# S4_-_MICROCONTROLLER.net
KiCad netlist of a schematic drawn in Altium Designer
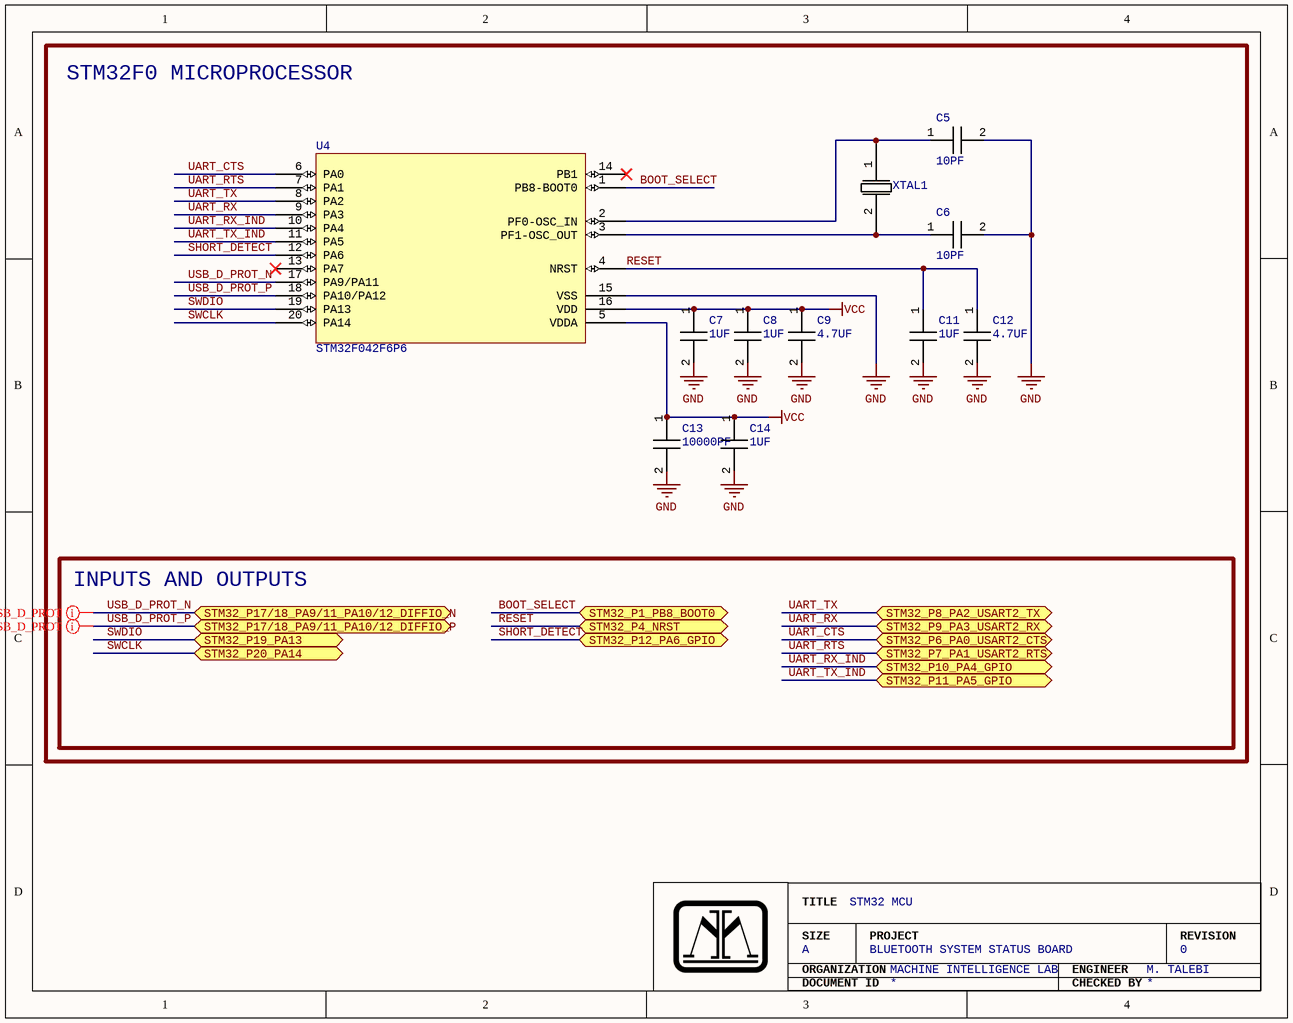
[diagram p0: S4 - MICROCONTROLLER.SchDoc]

(export (version "E")
  (design (tool "Eeschema 10.0.6"))
  (components
    (comp (ref "C5")
      (value "10PF")
      (footprint "C0603C0G1E100D030BA")
      (description "CAP CER 10PF 25V C0G 0201")
      (fields (field (name "TOLERANCE") "±0.5pF"))
      (libsource (lib "Master") (part "C0603C0G1E100D030BA"))
    )
    (comp (ref "C6")
      (value "10PF")
      (footprint "C0603C0G1E100D030BA")
      (description "CAP CER 10PF 25V C0G 0201")
      (fields (field (name "TOLERANCE") "±0.5pF"))
      (libsource (lib "Master") (part "C0603C0G1E100D030BA"))
    )
    (comp (ref "C7")
      (value "1UF")
      (footprint "CL10A105KQ8NNNC")
      (description "CAP CER 1UF 6.3V X5R 0603")
      (fields (field (name "TOLERANCE") "±10%"))
      (libsource (lib "Master") (part "CL10A105KQ8NNNC"))
    )
    (comp (ref "C8")
      (value "1UF")
      (footprint "CL10A105KQ8NNNC")
      (description "CAP CER 1UF 6.3V X5R 0603")
      (fields (field (name "TOLERANCE") "±10%"))
      (libsource (lib "Master") (part "CL10A105KQ8NNNC"))
    )
    (comp (ref "C9")
      (value "4.7UF")
      (footprint "TMK212AB7475KG-T")
      (description "CAP CER 4.7UF 25V X7R 0805")
      (fields (field (name "TOLERANCE") "±10%"))
      (libsource (lib "Master") (part "TMK212AB7475KG-T"))
    )
    (comp (ref "C11")
      (value "1UF")
      (footprint "CL10A105KQ8NNNC")
      (description "CAP CER 1UF 6.3V X5R 0603")
      (fields (field (name "TOLERANCE") "±10%"))
      (libsource (lib "Master") (part "CL10A105KQ8NNNC"))
    )
    (comp (ref "C12")
      (value "4.7UF")
      (footprint "TMK212AB7475KG-T")
      (description "CAP CER 4.7UF 25V X7R 0805")
      (fields (field (name "TOLERANCE") "±10%"))
      (libsource (lib "Master") (part "TMK212AB7475KG-T"))
    )
    (comp (ref "C13")
      (value "10000PF")
      (footprint "C1005X7R1C103K050BA")
      (description "CAP CER 10000PF 16V X7R 0402")
      (fields (field (name "TOLERANCE") "±10%"))
      (libsource (lib "Master") (part "C1005X7R1C103K050BA"))
    )
    (comp (ref "C14")
      (value "1UF")
      (footprint "CL10A105KQ8NNNC")
      (description "CAP CER 1UF 6.3V X5R 0603")
      (fields (field (name "TOLERANCE") "±10%"))
      (libsource (lib "Master") (part "CL10A105KQ8NNNC"))
    )
    (comp (ref "U4")
      (value "STM32F042F6P6")
      (footprint "STM32F042F6P6")
      (description "IC MCU 32BIT 32KB FLASH 20TSSOP")
      (libsource (lib "Master") (part "STM32F042F6P6"))
    )
    (comp (ref "XTAL1")
      (value "ECS-80-20-5PX-TR")
      (footprint "ECS-80-20-5PX-TR")
      (description "CRYSTAL 8.0000MHZ 20PF SMD")
      (libsource (lib "Master") (part "ECS-80-20-5PX-TR"))
    )
  )
  (nets
    (net (code "1") (name "/BOOT_SELECT") (class "Default")
      (node (ref "U4") (pin "1") (pinfunction "PB8-BOOT0_1") (pintype "bidirectional"))
    )
    (net (code "2") (name "/RESET") (class "Default")
      (node (ref "C11") (pin "1") (pinfunction "1_1") (pintype "passive"))
      (node (ref "C12") (pin "1") (pinfunction "1_1") (pintype "passive"))
      (node (ref "U4") (pin "4") (pinfunction "NRST_4") (pintype "bidirectional"))
    )
    (net (code "3") (name "/SHORT_DETECT") (class "Default")
      (node (ref "U4") (pin "12") (pinfunction "PA6_12") (pintype "bidirectional"))
    )
    (net (code "4") (name "/SWCLK") (class "Default")
      (node (ref "U4") (pin "20") (pinfunction "PA14_20") (pintype "bidirectional"))
    )
    (net (code "5") (name "/SWDIO") (class "Default")
      (node (ref "U4") (pin "19") (pinfunction "PA13_19") (pintype "bidirectional"))
    )
    (net (code "6") (name "/UART_CTS") (class "Default")
      (node (ref "U4") (pin "6") (pinfunction "PA0_6") (pintype "bidirectional"))
    )
    (net (code "7") (name "/UART_RTS") (class "Default")
      (node (ref "U4") (pin "7") (pinfunction "PA1_7") (pintype "bidirectional"))
    )
    (net (code "8") (name "/UART_RX") (class "Default")
      (node (ref "U4") (pin "9") (pinfunction "PA3_9") (pintype "bidirectional"))
    )
    (net (code "9") (name "/UART_RX_IND") (class "Default")
      (node (ref "U4") (pin "10") (pinfunction "PA4_10") (pintype "bidirectional"))
    )
    (net (code "10") (name "/UART_TX") (class "Default")
      (node (ref "U4") (pin "8") (pinfunction "PA2_8") (pintype "bidirectional"))
    )
    (net (code "11") (name "/UART_TX_IND") (class "Default")
      (node (ref "U4") (pin "11") (pinfunction "PA5_11") (pintype "bidirectional"))
    )
    (net (code "12") (name "/USB_D_PROT_N") (class "Default")
      (node (ref "U4") (pin "17") (pinfunction "PA9/PA11_17") (pintype "bidirectional"))
    )
    (net (code "13") (name "/USB_D_PROT_P") (class "Default")
      (node (ref "U4") (pin "18") (pinfunction "PA10/PA12_18") (pintype "bidirectional"))
    )
    (net (code "14") (name "GND") (class "Default")
      (node (ref "C11") (pin "2") (pinfunction "2_2") (pintype "passive"))
      (node (ref "C12") (pin "2") (pinfunction "2_2") (pintype "passive"))
      (node (ref "C13") (pin "2") (pinfunction "2_2") (pintype "passive"))
      (node (ref "C14") (pin "2") (pinfunction "2_2") (pintype "passive"))
      (node (ref "C5") (pin "2") (pinfunction "2_2") (pintype "passive"))
      (node (ref "C6") (pin "2") (pinfunction "2_2") (pintype "passive"))
      (node (ref "C7") (pin "2") (pinfunction "2_2") (pintype "passive"))
      (node (ref "C8") (pin "2") (pinfunction "2_2") (pintype "passive"))
      (node (ref "C9") (pin "2") (pinfunction "2_2") (pintype "passive"))
      (node (ref "U4") (pin "15") (pinfunction "VSS_15") (pintype "power_in"))
    )
    (net (code "15") (name "Net-(U4-PF0-OSC_IN)") (class "Default")
      (node (ref "C5") (pin "1") (pinfunction "1_1") (pintype "passive"))
      (node (ref "U4") (pin "2") (pinfunction "PF0-OSC_IN_2") (pintype "bidirectional"))
      (node (ref "XTAL1") (pin "1") (pinfunction "1_1") (pintype "passive"))
    )
    (net (code "16") (name "Net-(U4-PF1-OSC_OUT)") (class "Default")
      (node (ref "C6") (pin "1") (pinfunction "1_1") (pintype "passive"))
      (node (ref "U4") (pin "3") (pinfunction "PF1-OSC_OUT_3") (pintype "bidirectional"))
      (node (ref "XTAL1") (pin "2") (pinfunction "2_2") (pintype "passive"))
    )
    (net (code "17") (name "VCC") (class "Default")
      (node (ref "C13") (pin "1") (pinfunction "1_1") (pintype "passive"))
      (node (ref "C14") (pin "1") (pinfunction "1_1") (pintype "passive"))
      (node (ref "C7") (pin "1") (pinfunction "1_1") (pintype "passive"))
      (node (ref "C8") (pin "1") (pinfunction "1_1") (pintype "passive"))
      (node (ref "C9") (pin "1") (pinfunction "1_1") (pintype "passive"))
      (node (ref "U4") (pin "16") (pinfunction "VDD_16") (pintype "power_in"))
      (node (ref "U4") (pin "5") (pinfunction "VDDA_5") (pintype "power_in"))
    )
    (net (code "18") (name "unconnected-(U4-PA7-Pad13)") (class "Default")
      (node (ref "U4") (pin "13") (pinfunction "PA7_13") (pintype "bidirectional+no_connect"))
    )
    (net (code "19") (name "unconnected-(U4-PB1-Pad14)") (class "Default")
      (node (ref "U4") (pin "14") (pinfunction "PB1_14") (pintype "bidirectional+no_connect"))
    )
  )
)
